# BLL-EBOOK-RpiZero.net
KiCad netlist of a schematic drawn in EAGLE
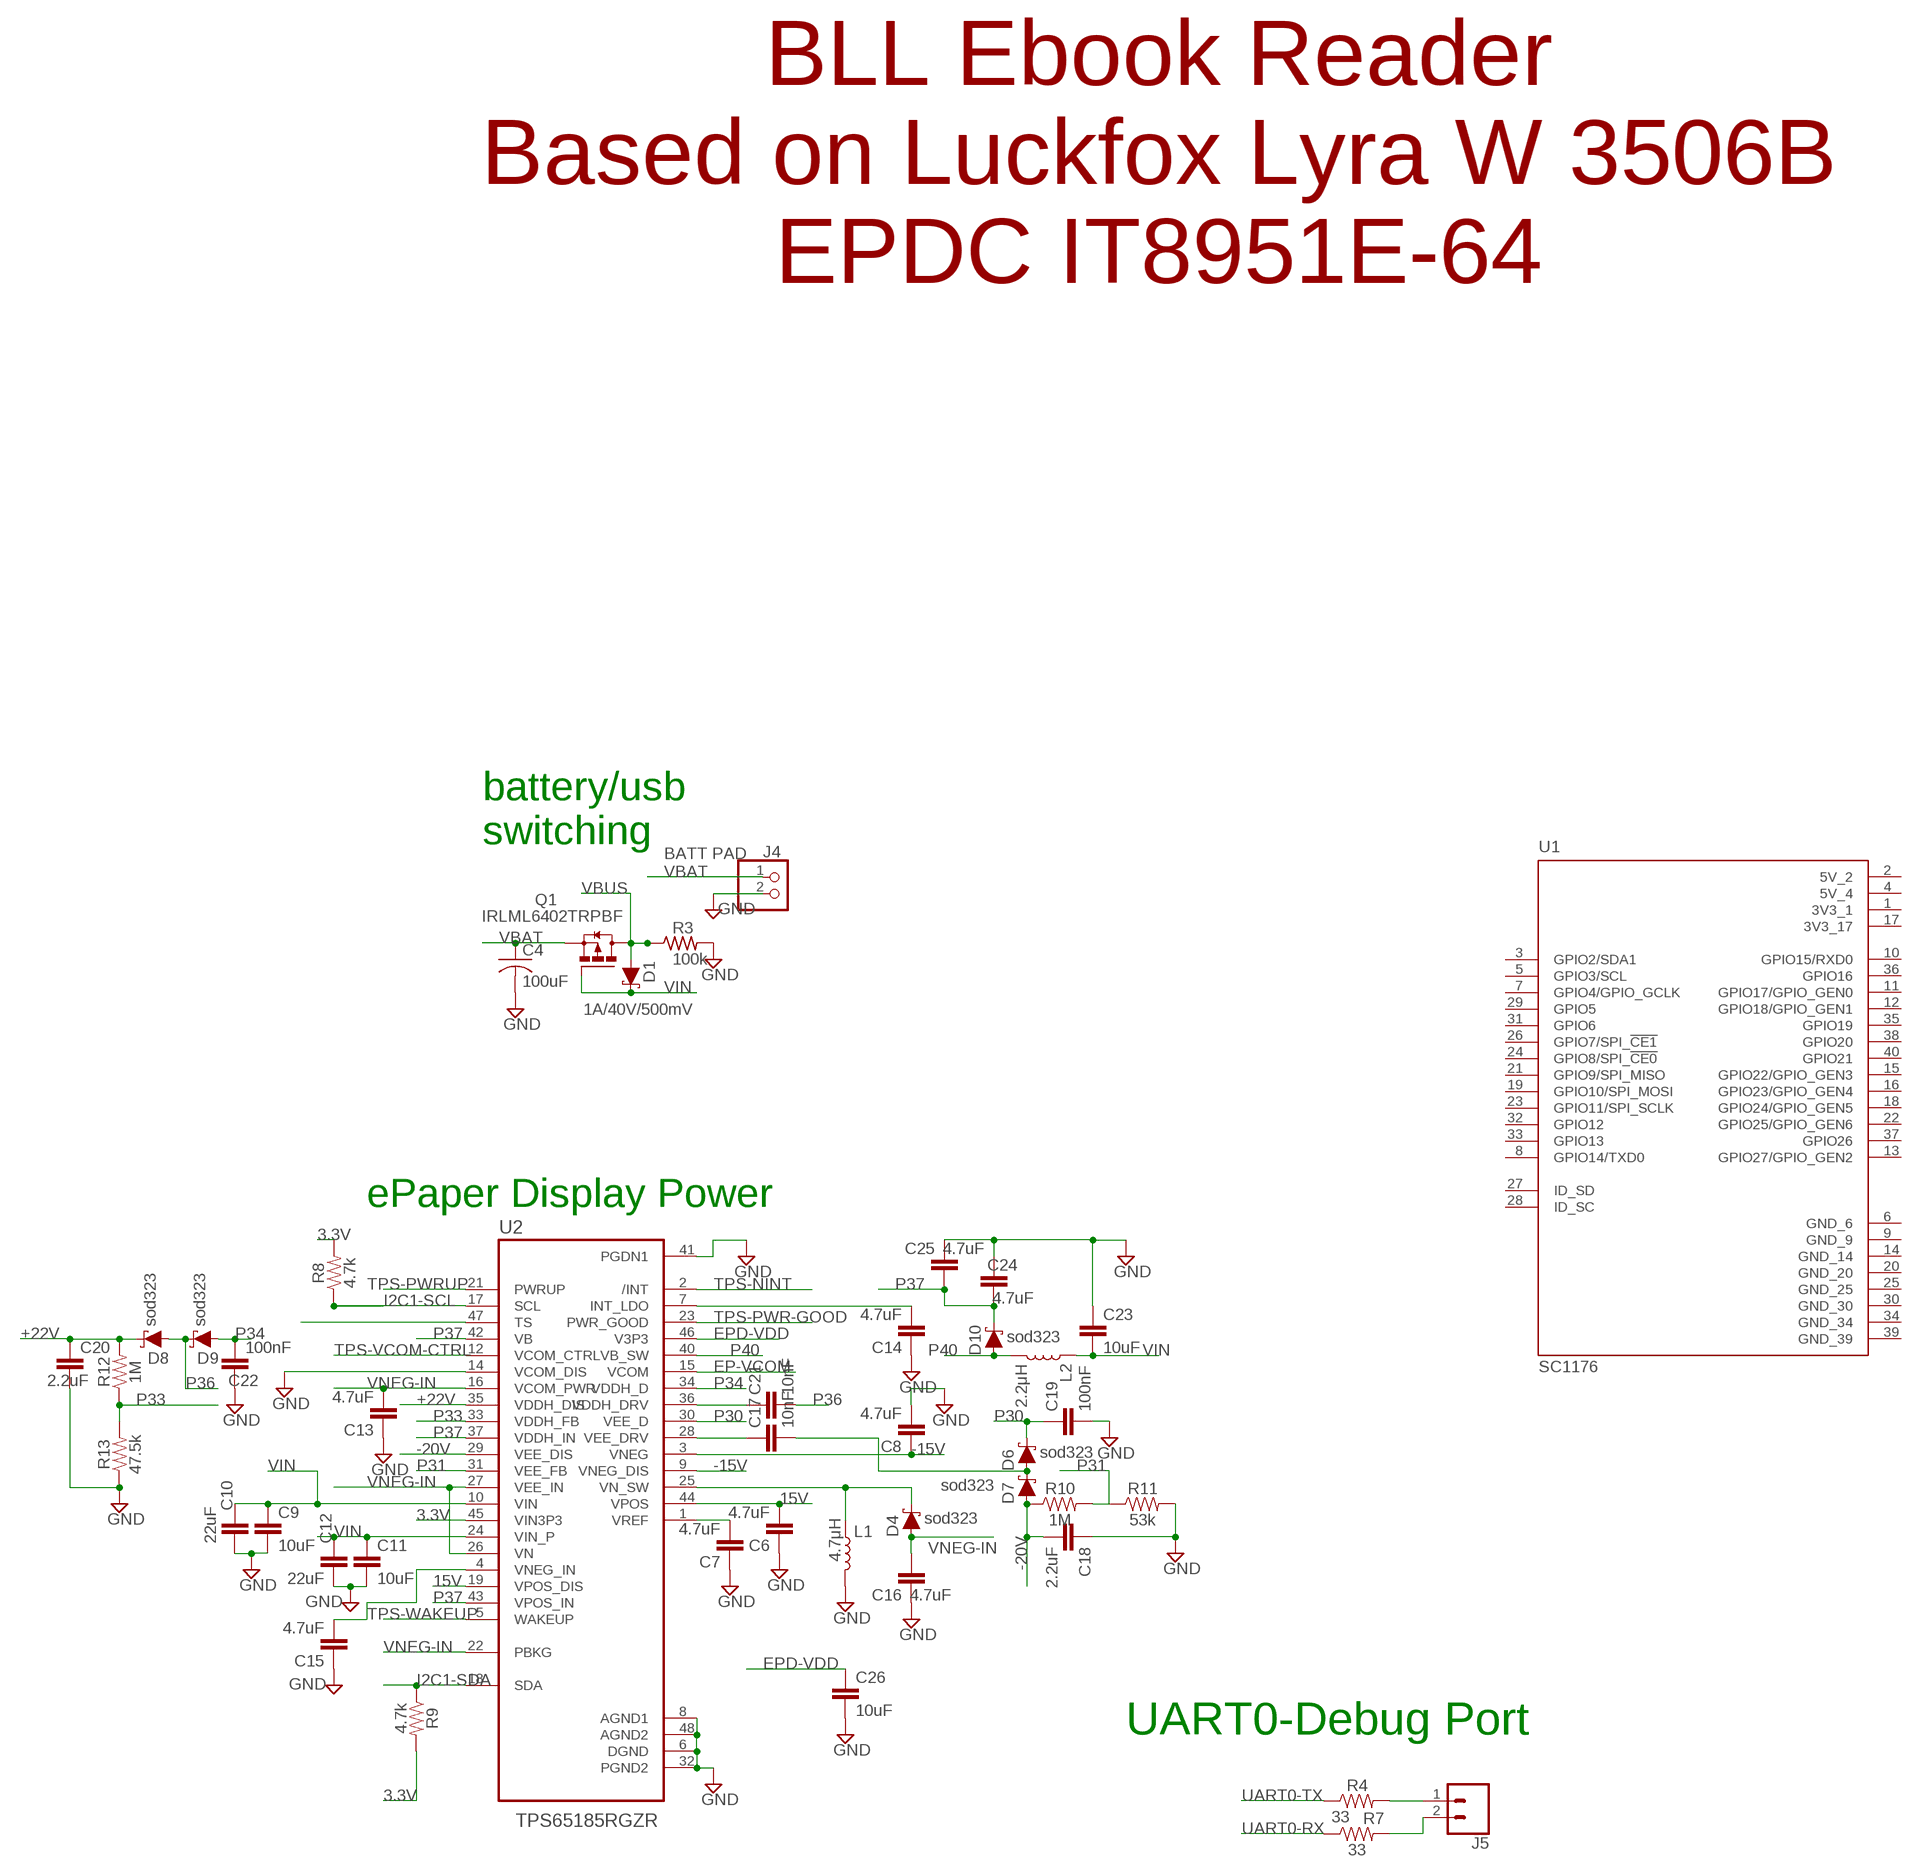
[diagram p0: schematic, sheet 1, part 1 of 2]
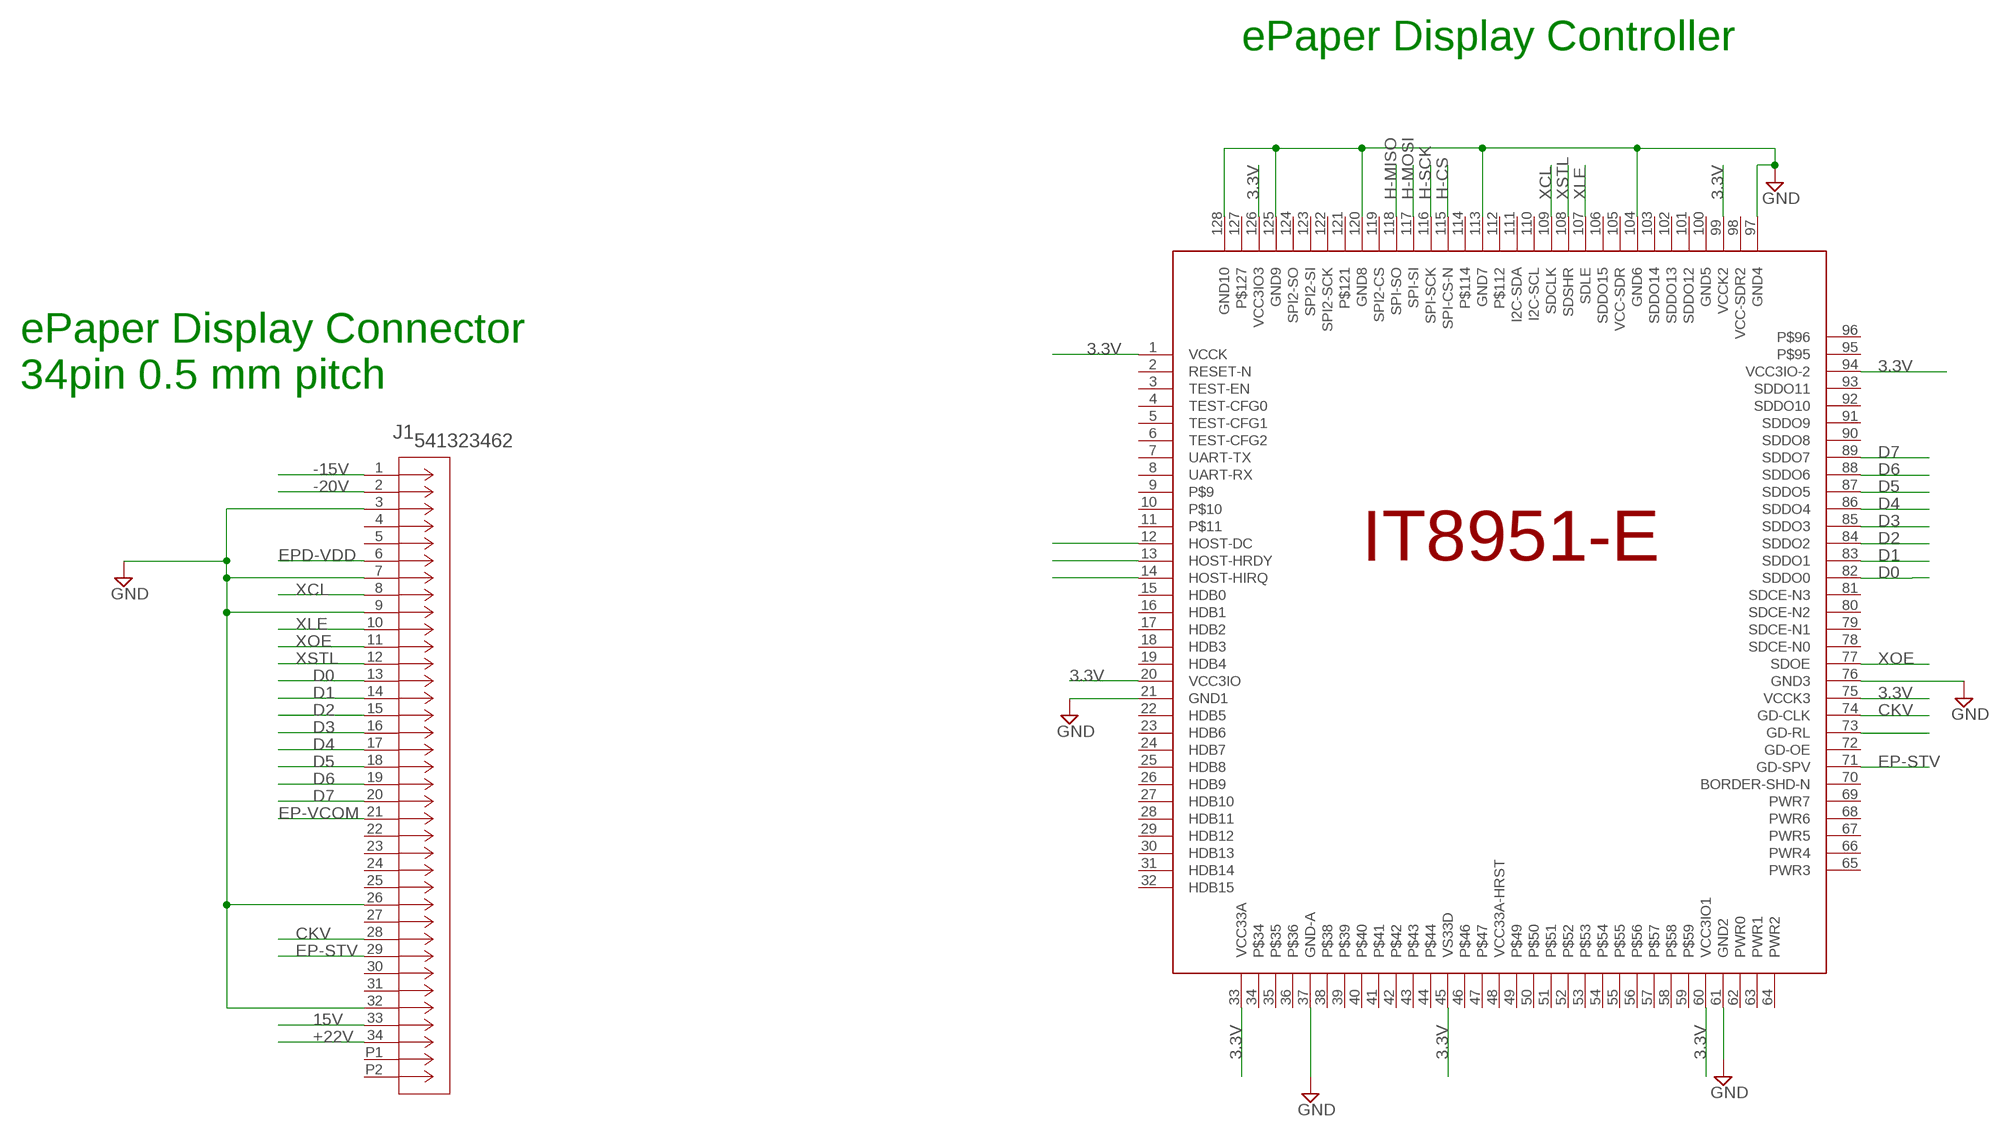
[diagram p1: schematic, sheet 1, part 2 of 2]

(export (version "E")
  (design (tool "Eeschema 10.0.6"))
  (components
    (comp (ref "C4")
      (value "100uF")
      (footprint "eagle-import:C0603")
      (libsource (lib "eagle-import") (part "C-USC0603"))
    )
    (comp (ref "C6")
      (value "4.7uF")
      (footprint "eagle-import:0603")
      (libsource (lib "eagle-import") (part "4.7UF-0603-35V-(20%)"))
    )
    (comp (ref "C7")
      (value "4.7uF")
      (footprint "eagle-import:0603")
      (libsource (lib "eagle-import") (part "4.7UF-0603-35V-(20%)"))
    )
    (comp (ref "C8")
      (value "4.7uF")
      (footprint "eagle-import:0603")
      (libsource (lib "eagle-import") (part "4.7UF-0603-35V-(20%)"))
    )
    (comp (ref "C9")
      (value "10uF")
      (footprint "eagle-import:0805")
      (libsource (lib "eagle-import") (part "10UF-0805-10V-10%"))
    )
    (comp (ref "C10")
      (value "22uF")
      (footprint "eagle-import:0805")
      (libsource (lib "eagle-import") (part "22UF-0805-16V-20%"))
    )
    (comp (ref "C11")
      (value "10uF")
      (footprint "eagle-import:0805")
      (libsource (lib "eagle-import") (part "10UF-0805-10V-10%"))
    )
    (comp (ref "C12")
      (value "22uF")
      (footprint "eagle-import:0805")
      (libsource (lib "eagle-import") (part "22UF-0805-16V-20%"))
    )
    (comp (ref "C13")
      (value "4.7uF")
      (footprint "eagle-import:0603")
      (libsource (lib "eagle-import") (part "4.7UF-0603-35V-(20%)"))
    )
    (comp (ref "C14")
      (value "4.7uF")
      (footprint "eagle-import:0603")
      (libsource (lib "eagle-import") (part "4.7UF-0603-35V-(20%)"))
    )
    (comp (ref "C15")
      (value "4.7uF")
      (footprint "eagle-import:0603")
      (libsource (lib "eagle-import") (part "4.7UF-0603-35V-(20%)"))
    )
    (comp (ref "C16")
      (value "4.7uF")
      (footprint "eagle-import:0603")
      (libsource (lib "eagle-import") (part "4.7UF-0603-35V-(20%)"))
    )
    (comp (ref "C17")
      (value "10nF")
      (footprint "eagle-import:0603")
      (libsource (lib "eagle-import") (part "10NF-0603-50V-10%"))
    )
    (comp (ref "C18")
      (value "2.2uF")
      (footprint "eagle-import:1206")
      (libsource (lib "eagle-import") (part "2.2UF-1206-50V-10%"))
    )
    (comp (ref "C19")
      (value "100nF")
      (footprint "eagle-import:0603")
      (libsource (lib "eagle-import") (part "DNP-0603"))
    )
    (comp (ref "C20")
      (value "2.2uF")
      (footprint "eagle-import:1206")
      (libsource (lib "eagle-import") (part "2.2UF-1206-50V-10%"))
    )
    (comp (ref "C21")
      (value "10nF")
      (footprint "eagle-import:0603")
      (libsource (lib "eagle-import") (part "10NF-0603-50V-10%"))
    )
    (comp (ref "C22")
      (value "100nF")
      (footprint "eagle-import:0603")
      (libsource (lib "eagle-import") (part "DNP-0603"))
    )
    (comp (ref "C23")
      (value "10uF")
      (footprint "eagle-import:0805")
      (libsource (lib "eagle-import") (part "10UF-0805-10V-10%"))
    )
    (comp (ref "C24")
      (value "4.7uF")
      (footprint "eagle-import:0603")
      (libsource (lib "eagle-import") (part "4.7UF-0603-35V-(20%)"))
    )
    (comp (ref "C25")
      (value "4.7uF")
      (footprint "eagle-import:0603")
      (libsource (lib "eagle-import") (part "4.7UF-0603-35V-(20%)"))
    )
    (comp (ref "C26")
      (value "10uF")
      (footprint "eagle-import:0805")
      (libsource (lib "eagle-import") (part "10UF-0805-10V-10%"))
    )
    (comp (ref "D1")
      (value "1A/40V/500mV")
      (footprint "eagle-import:SMA-DIODE")
      (libsource (lib "eagle-import") (part "DIODE-SCHOTTKY-SS14"))
    )
    (comp (ref "D4")
      (value "sod323")
      (footprint "eagle-import:SOD-323")
      (libsource (lib "eagle-import") (part "DIODE-SCHOTTKY-PMEG4005EJ"))
    )
    (comp (ref "D6")
      (value "sod323")
      (footprint "eagle-import:SOD-323")
      (libsource (lib "eagle-import") (part "DIODE-SCHOTTKY-PMEG4005EJ"))
    )
    (comp (ref "D7")
      (value "sod323")
      (footprint "eagle-import:SOD-323")
      (libsource (lib "eagle-import") (part "DIODE-SCHOTTKY-PMEG4005EJ"))
    )
    (comp (ref "D8")
      (value "sod323")
      (footprint "eagle-import:SOD-323")
      (libsource (lib "eagle-import") (part "DIODE-SCHOTTKY-PMEG4005EJ"))
    )
    (comp (ref "D9")
      (value "sod323")
      (footprint "eagle-import:SOD-323")
      (libsource (lib "eagle-import") (part "DIODE-SCHOTTKY-PMEG4005EJ"))
    )
    (comp (ref "D10")
      (value "sod323")
      (footprint "eagle-import:SOD-323")
      (libsource (lib "eagle-import") (part "DIODE-SCHOTTKY-PMEG4005EJ"))
    )
    (comp (ref "J1")
      (value "541323462")
      (footprint "eagle-import:CON_541323462_MOL")
      (fields (field (name "MF") "Molex"))
      (libsource (lib "eagle-import") (part "541323462"))
    )
    (comp (ref "J4")
      (value "BATT PAD")
      (footprint "eagle-import:1X02_90")
      (libsource (lib "eagle-import") (part "PINHD-1X2/90"))
    )
    (comp (ref "J5")
      (value "CONN_02LOCK")
      (footprint "eagle-import:1X02_LOCK")
      (libsource (lib "eagle-import") (part "CONN_02LOCK"))
    )
    (comp (ref "L1")
      (value "4.7μH")
      (footprint "eagle-import:1008(2520)")
      (libsource (lib "eagle-import") (part "4.7μH_SHIELDED_INDUCTOR"))
    )
    (comp (ref "L2")
      (value "2.2μH")
      (footprint "eagle-import:0806")
      (libsource (lib "eagle-import") (part "2.2μH_SHIELDED_INDUCTOR"))
    )
    (comp (ref "Q1")
      (value "IRLML6402TRPBF")
      (footprint "eagle-import:SOT23")
      (fields (field (name "MF") "Infineon Technologies") (field (name "MP") "IRLML6402"))
      (libsource (lib "eagle-import") (part "IRLML6402TRPBF"))
    )
    (comp (ref "R3")
      (value "100k")
      (footprint "eagle-import:R0603")
      (libsource (lib "eagle-import") (part "R-US_R0603"))
    )
    (comp (ref "R4")
      (value "33")
      (footprint "eagle-import:0603")
      (libsource (lib "eagle-import") (part "33OHM-0603-1/10W-1%"))
    )
    (comp (ref "R7")
      (value "33")
      (footprint "eagle-import:0603")
      (libsource (lib "eagle-import") (part "33OHM-0603-1/10W-1%"))
    )
    (comp (ref "R8")
      (value "4.7k")
      (footprint "eagle-import:0603")
      (libsource (lib "eagle-import") (part "4.7KOHM-0603-1/10W-1%"))
    )
    (comp (ref "R9")
      (value "4.7k")
      (footprint "eagle-import:0603")
      (libsource (lib "eagle-import") (part "4.7KOHM-0603-1/10W-1%"))
    )
    (comp (ref "R10")
      (value "1M")
      (footprint "eagle-import:0603")
      (libsource (lib "eagle-import") (part "1MOHM-0603-1/4W-5%"))
    )
    (comp (ref "R11")
      (value "53k")
      (footprint "eagle-import:0805")
      (libsource (lib "eagle-import") (part "RESISTOR0805"))
    )
    (comp (ref "R12")
      (value "1M")
      (footprint "eagle-import:0603")
      (libsource (lib "eagle-import") (part "1MOHM-0603-1/4W-5%"))
    )
    (comp (ref "R13")
      (value "47.5k")
      (footprint "eagle-import:0805")
      (libsource (lib "eagle-import") (part "RESISTOR0805"))
    )
    (comp (ref "U$1")
      (value "IT8951")
      (footprint "eagle-import:LQFP128_STM")
      (libsource (lib "eagle-import") (part "IT8951"))
    )
    (comp (ref "U1")
      (value "SC1176")
      (footprint "eagle-import:MODULE_SC1176")
      (fields (field (name "MF") "Raspberry Pi"))
      (libsource (lib "eagle-import") (part "SC1176"))
    )
    (comp (ref "U2")
      (value "TPS65185RGZR")
      (footprint "eagle-import:QFN50P700X700X100-49N")
      (fields (field (name "MF") "Texas Instruments"))
      (libsource (lib "eagle-import") (part "TPS65185RGZR"))
    )
  )
  (nets
    (net (code "1") (name "/+22V") (class "Default")
      (node (ref "C20") (pin "1") (pinfunction "1_1") (pintype "passive"))
      (node (ref "D8") (pin "C") (pinfunction "C_C") (pintype "passive"))
      (node (ref "J1") (pin "34") (pinfunction "34_34") (pintype "passive"))
      (node (ref "R12") (pin "2") (pinfunction "2_2") (pintype "passive"))
      (node (ref "U2") (pin "35") (pinfunction "VDDH_DIS_35") (pintype "input"))
    )
    (net (code "2") (name "/-15V") (class "Default")
      (node (ref "C8") (pin "1") (pinfunction "1_1") (pintype "passive"))
      (node (ref "J1") (pin "1") (pinfunction "1_1") (pintype "passive"))
      (node (ref "U2") (pin "3") (pinfunction "VNEG_3") (pintype "output"))
      (node (ref "U2") (pin "9") (pinfunction "VNEG_DIS_9") (pintype "output"))
    )
    (net (code "3") (name "/-20V") (class "Default")
      (node (ref "C18") (pin "2") (pinfunction "2_2") (pintype "passive"))
      (node (ref "D7") (pin "A") (pinfunction "A_A") (pintype "passive"))
      (node (ref "J1") (pin "2") (pinfunction "2_2") (pintype "passive"))
      (node (ref "R10") (pin "1") (pinfunction "1_1") (pintype "passive"))
      (node (ref "U2") (pin "29") (pinfunction "VEE_DIS_29") (pintype "input"))
    )
    (net (code "4") (name "/3.3V") (class "Default")
      (node (ref "R8") (pin "2") (pinfunction "2_2") (pintype "passive"))
      (node (ref "R9") (pin "2") (pinfunction "2_2") (pintype "passive"))
      (node (ref "U$1") (pin "1") (pinfunction "VCCK_1") (pintype "bidirectional"))
      (node (ref "U$1") (pin "126") (pinfunction "VCC3IO3_126") (pintype "bidirectional"))
      (node (ref "U$1") (pin "20") (pinfunction "VCC3IO_20") (pintype "bidirectional"))
      (node (ref "U$1") (pin "33") (pinfunction "VCC33A_33") (pintype "bidirectional"))
      (node (ref "U$1") (pin "45") (pinfunction "VS33D_45") (pintype "bidirectional"))
      (node (ref "U$1") (pin "60") (pinfunction "VCC3IO1_60") (pintype "bidirectional"))
      (node (ref "U$1") (pin "75") (pinfunction "VCCK3_75") (pintype "bidirectional"))
      (node (ref "U$1") (pin "94") (pinfunction "VCC3IO-2_94") (pintype "bidirectional"))
      (node (ref "U$1") (pin "99") (pinfunction "VCCK2_99") (pintype "bidirectional"))
      (node (ref "U2") (pin "45") (pinfunction "VIN3P3_45") (pintype "input"))
    )
    (net (code "5") (name "/3V3_1") (class "Default")
      (node (ref "U1") (pin "1") (pinfunction "3V3_1_1") (pintype "power_in"))
    )
    (net (code "6") (name "/3V3_17") (class "Default")
      (node (ref "U1") (pin "17") (pinfunction "3V3_17_17") (pintype "power_in"))
    )
    (net (code "7") (name "/5V_2") (class "Default")
      (node (ref "U1") (pin "2") (pinfunction "5V_2_2") (pintype "power_in"))
    )
    (net (code "8") (name "/5V_4") (class "Default")
      (node (ref "U1") (pin "4") (pinfunction "5V_4_4") (pintype "power_in"))
    )
    (net (code "9") (name "/15V") (class "Default")
      (node (ref "C6") (pin "2") (pinfunction "2_2") (pintype "passive"))
      (node (ref "J1") (pin "33") (pinfunction "33_33") (pintype "passive"))
      (node (ref "U2") (pin "19") (pinfunction "VPOS_DIS_19") (pintype "input"))
      (node (ref "U2") (pin "44") (pinfunction "VPOS_44") (pintype "output"))
    )
    (net (code "10") (name "/CKV") (class "Default")
      (node (ref "J1") (pin "28") (pinfunction "28_28") (pintype "passive"))
      (node (ref "U$1") (pin "74") (pinfunction "GD-CLK_74") (pintype "bidirectional"))
    )
    (net (code "11") (name "/D0") (class "Default")
      (node (ref "J1") (pin "13") (pinfunction "13_13") (pintype "passive"))
      (node (ref "U$1") (pin "82") (pinfunction "SDDO0_82") (pintype "bidirectional"))
    )
    (net (code "12") (name "/D1") (class "Default")
      (node (ref "J1") (pin "14") (pinfunction "14_14") (pintype "passive"))
      (node (ref "U$1") (pin "83") (pinfunction "SDDO1_83") (pintype "bidirectional"))
    )
    (net (code "13") (name "/D2") (class "Default")
      (node (ref "J1") (pin "15") (pinfunction "15_15") (pintype "passive"))
      (node (ref "U$1") (pin "84") (pinfunction "SDDO2_84") (pintype "bidirectional"))
    )
    (net (code "14") (name "/D3") (class "Default")
      (node (ref "J1") (pin "16") (pinfunction "16_16") (pintype "passive"))
      (node (ref "U$1") (pin "85") (pinfunction "SDDO3_85") (pintype "bidirectional"))
    )
    (net (code "15") (name "/D4") (class "Default")
      (node (ref "J1") (pin "17") (pinfunction "17_17") (pintype "passive"))
      (node (ref "U$1") (pin "86") (pinfunction "SDDO4_86") (pintype "bidirectional"))
    )
    (net (code "16") (name "/D5") (class "Default")
      (node (ref "J1") (pin "18") (pinfunction "18_18") (pintype "passive"))
      (node (ref "U$1") (pin "87") (pinfunction "SDDO5_87") (pintype "bidirectional"))
    )
    (net (code "17") (name "/D6") (class "Default")
      (node (ref "J1") (pin "19") (pinfunction "19_19") (pintype "passive"))
      (node (ref "U$1") (pin "88") (pinfunction "SDDO6_88") (pintype "bidirectional"))
    )
    (net (code "18") (name "/D7") (class "Default")
      (node (ref "J1") (pin "20") (pinfunction "20_20") (pintype "passive"))
      (node (ref "U$1") (pin "89") (pinfunction "SDDO7_89") (pintype "bidirectional"))
    )
    (net (code "19") (name "/EP-STV") (class "Default")
      (node (ref "J1") (pin "29") (pinfunction "29_29") (pintype "passive"))
      (node (ref "U$1") (pin "71") (pinfunction "GD-SPV_71") (pintype "bidirectional"))
    )
    (net (code "20") (name "/EP-VCOM") (class "Default")
      (node (ref "J1") (pin "21") (pinfunction "21_21") (pintype "passive"))
      (node (ref "U2") (pin "15") (pinfunction "VCOM_15") (pintype "output"))
    )
    (net (code "21") (name "/EPD-VDD") (class "Default")
      (node (ref "C26") (pin "1") (pinfunction "1_1") (pintype "passive"))
      (node (ref "J1") (pin "6") (pinfunction "6_6") (pintype "passive"))
      (node (ref "U2") (pin "46") (pinfunction "V3P3_46") (pintype "output"))
    )
    (net (code "22") (name "/GND_6") (class "Default")
      (node (ref "U1") (pin "6") (pinfunction "GND_6_6") (pintype "power_in"))
    )
    (net (code "23") (name "/GND_9") (class "Default")
      (node (ref "U1") (pin "9") (pinfunction "GND_9_9") (pintype "power_in"))
    )
    (net (code "24") (name "/GND_14") (class "Default")
      (node (ref "U1") (pin "14") (pinfunction "GND_14_14") (pintype "power_in"))
    )
    (net (code "25") (name "/GND_20") (class "Default")
      (node (ref "U1") (pin "20") (pinfunction "GND_20_20") (pintype "power_in"))
    )
    (net (code "26") (name "/GND_25") (class "Default")
      (node (ref "U1") (pin "25") (pinfunction "GND_25_25") (pintype "power_in"))
    )
    (net (code "27") (name "/GND_30") (class "Default")
      (node (ref "U1") (pin "30") (pinfunction "GND_30_30") (pintype "power_in"))
    )
    (net (code "28") (name "/GND_34") (class "Default")
      (node (ref "U1") (pin "34") (pinfunction "GND_34_34") (pintype "power_in"))
    )
    (net (code "29") (name "/GND_39") (class "Default")
      (node (ref "U1") (pin "39") (pinfunction "GND_39_39") (pintype "power_in"))
    )
    (net (code "30") (name "/H-CS") (class "Default")
      (node (ref "U$1") (pin "115") (pinfunction "SPI-CS-N_115") (pintype "bidirectional"))
    )
    (net (code "31") (name "/H-MISO") (class "Default")
      (node (ref "U$1") (pin "118") (pinfunction "SPI-SO_118") (pintype "bidirectional"))
    )
    (net (code "32") (name "/H-MOSI") (class "Default")
      (node (ref "U$1") (pin "117") (pinfunction "SPI-SI_117") (pintype "bidirectional"))
    )
    (net (code "33") (name "/H-SCK") (class "Default")
      (node (ref "U$1") (pin "116") (pinfunction "SPI-SCK_116") (pintype "bidirectional"))
    )
    (net (code "34") (name "/I2C1-SCL") (class "Default")
      (node (ref "R8") (pin "1") (pinfunction "1_1") (pintype "passive"))
      (node (ref "U2") (pin "17") (pinfunction "SCL_17") (pintype "input"))
    )
    (net (code "35") (name "/I2C1-SDA") (class "Default")
      (node (ref "R9") (pin "1") (pinfunction "1_1") (pintype "passive"))
      (node (ref "U2") (pin "18") (pinfunction "SDA_18") (pintype "bidirectional"))
    )
    (net (code "36") (name "/P30") (class "Default")
      (node (ref "C19") (pin "1") (pinfunction "1_1") (pintype "passive"))
      (node (ref "D6") (pin "C") (pinfunction "C_C") (pintype "passive"))
      (node (ref "U2") (pin "30") (pinfunction "VEE_D_30") (pintype "output"))
    )
    (net (code "37") (name "/P31") (class "Default")
      (node (ref "R10") (pin "2") (pinfunction "2_2") (pintype "passive"))
      (node (ref "R11") (pin "1") (pinfunction "1_1") (pintype "passive"))
      (node (ref "U2") (pin "31") (pinfunction "VEE_FB_31") (pintype "input"))
    )
    (net (code "38") (name "/P33") (class "Default")
      (node (ref "R12") (pin "1") (pinfunction "1_1") (pintype "passive"))
      (node (ref "R13") (pin "2") (pinfunction "2_2") (pintype "passive"))
      (node (ref "U2") (pin "33") (pinfunction "VDDH_FB_33") (pintype "input"))
    )
    (net (code "39") (name "/P34") (class "Default")
      (node (ref "C22") (pin "2") (pinfunction "2_2") (pintype "passive"))
      (node (ref "D9") (pin "A") (pinfunction "A_A") (pintype "passive"))
      (node (ref "U2") (pin "34") (pinfunction "VDDH_D_34") (pintype "output"))
    )
    (net (code "40") (name "/P36") (class "Default")
      (node (ref "C21") (pin "2") (pinfunction "2_2") (pintype "passive"))
      (node (ref "D8") (pin "A") (pinfunction "A_A") (pintype "passive"))
      (node (ref "D9") (pin "C") (pinfunction "C_C") (pintype "passive"))
    )
    (net (code "41") (name "/P37") (class "Default")
      (node (ref "C24") (pin "1") (pinfunction "1_1") (pintype "passive"))
      (node (ref "C25") (pin "1") (pinfunction "1_1") (pintype "passive"))
      (node (ref "D10") (pin "C") (pinfunction "C_C") (pintype "passive"))
      (node (ref "U2") (pin "37") (pinfunction "VDDH_IN_37") (pintype "input"))
      (node (ref "U2") (pin "42") (pinfunction "VB_42") (pintype "input"))
      (node (ref "U2") (pin "43") (pinfunction "VPOS_IN_43") (pintype "input"))
    )
    (net (code "42") (name "/P40") (class "Default")
      (node (ref "D10") (pin "A") (pinfunction "A_A") (pintype "passive"))
      (node (ref "L2") (pin "2") (pinfunction "2_2") (pintype "passive"))
      (node (ref "U2") (pin "40") (pinfunction "VB_SW_40") (pintype "output"))
    )
    (net (code "43") (name "/TPS-NINT") (class "Default")
      (node (ref "U2") (pin "2") (pinfunction "/INT_2") (pintype "output"))
    )
    (net (code "44") (name "/TPS-PWR-GOOD") (class "Default")
      (node (ref "U2") (pin "23") (pinfunction "PWR_GOOD_23") (pintype "output"))
    )
    (net (code "45") (name "/TPS-PWRUP") (class "Default")
      (node (ref "U2") (pin "21") (pinfunction "PWRUP_21") (pintype "input"))
    )
    (net (code "46") (name "/TPS-VCOM-CTRL") (class "Default")
      (node (ref "U2") (pin "12") (pinfunction "VCOM_CTRL_12") (pintype "input"))
    )
    (net (code "47") (name "/TPS-WAKEUP") (class "Default")
      (node (ref "U2") (pin "5") (pinfunction "WAKEUP_5") (pintype "input"))
    )
    (net (code "48") (name "/UART0-RX") (class "Default")
      (node (ref "R7") (pin "1") (pinfunction "1_1") (pintype "passive"))
    )
    (net (code "49") (name "/UART0-TX") (class "Default")
      (node (ref "R4") (pin "1") (pinfunction "1_1") (pintype "passive"))
    )
    (net (code "50") (name "/VBAT") (class "Default")
      (node (ref "C4") (pin "1") (pinfunction "1_1") (pintype "passive"))
      (node (ref "J4") (pin "1") (pinfunction "1_1") (pintype "passive"))
      (node (ref "Q1") (pin "2") (pinfunction "S_2") (pintype "passive"))
    )
    (net (code "51") (name "/VBUS") (class "Default")
      (node (ref "D1") (pin "A") (pinfunction "A_A") (pintype "passive"))
      (node (ref "Q1") (pin "3") (pinfunction "D_3") (pintype "passive"))
      (node (ref "R3") (pin "1") (pinfunction "1_1") (pintype "passive"))
    )
    (net (code "52") (name "/VIN") (class "Default")
      (node (ref "C10") (pin "1") (pinfunction "1_1") (pintype "passive"))
      (node (ref "C11") (pin "1") (pinfunction "1_1") (pintype "passive"))
      (node (ref "C12") (pin "1") (pinfunction "1_1") (pintype "passive"))
      (node (ref "C23") (pin "2") (pinfunction "2_2") (pintype "passive"))
      (node (ref "C9") (pin "1") (pinfunction "1_1") (pintype "passive"))
      (node (ref "D1") (pin "C") (pinfunction "C_C") (pintype "passive"))
      (node (ref "L2") (pin "1") (pinfunction "1_1") (pintype "passive"))
      (node (ref "Q1") (pin "1") (pinfunction "G_1") (pintype "passive"))
      (node (ref "U2") (pin "10") (pinfunction "VIN_10") (pintype "input"))
      (node (ref "U2") (pin "24") (pinfunction "VIN_P_24") (pintype "input"))
    )
    (net (code "53") (name "/VNEG-IN") (class "Default")
      (node (ref "C13") (pin "2") (pinfunction "2_2") (pintype "passive"))
      (node (ref "C16") (pin "2") (pinfunction "2_2") (pintype "passive"))
      (node (ref "D4") (pin "A") (pinfunction "A_A") (pintype "passive"))
      (node (ref "U2") (pin "16") (pinfunction "VCOM_PWR_16") (pintype "input"))
      (node (ref "U2") (pin "22") (pinfunction "PBKG_22") (pintype "bidirectional"))
      (node (ref "U2") (pin "26") (pinfunction "VN_26") (pintype "input"))
      (node (ref "U2") (pin "27") (pinfunction "VEE_IN_27") (pintype "input"))
    )
    (net (code "54") (name "/XCL") (class "Default")
      (node (ref "J1") (pin "8") (pinfunction "8_8") (pintype "passive"))
      (node (ref "U$1") (pin "109") (pinfunction "SDCLK_109") (pintype "bidirectional"))
    )
    (net (code "55") (name "/XLE") (class "Default")
      (node (ref "J1") (pin "10") (pinfunction "10_10") (pintype "passive"))
      (node (ref "U$1") (pin "107") (pinfunction "SDLE_107") (pintype "bidirectional"))
    )
    (net (code "56") (name "/XOE") (class "Default")
      (node (ref "J1") (pin "11") (pinfunction "11_11") (pintype "passive"))
      (node (ref "U$1") (pin "77") (pinfunction "SDOE_77") (pintype "bidirectional"))
    )
    (net (code "57") (name "/XSTL") (class "Default")
      (node (ref "J1") (pin "12") (pinfunction "12_12") (pintype "passive"))
      (node (ref "U$1") (pin "108") (pinfunction "SDSHR_108") (pintype "bidirectional"))
    )
    (net (code "58") (name "GND") (class "Default")
      (node (ref "C10") (pin "2") (pinfunction "2_2") (pintype "passive"))
      (node (ref "C11") (pin "2") (pinfunction "2_2") (pintype "passive"))
      (node (ref "C12") (pin "2") (pinfunction "2_2") (pintype "passive"))
      (node (ref "C13") (pin "1") (pinfunction "1_1") (pintype "passive"))
      (node (ref "C14") (pin "1") (pinfunction "1_1") (pintype "passive"))
      (node (ref "C15") (pin "1") (pinfunction "1_1") (pintype "passive"))
      (node (ref "C16") (pin "1") (pinfunction "1_1") (pintype "passive"))
      (node (ref "C18") (pin "1") (pinfunction "1_1") (pintype "passive"))
      (node (ref "C19") (pin "2") (pinfunction "2_2") (pintype "passive"))
      (node (ref "C20") (pin "2") (pinfunction "2_2") (pintype "passive"))
      (node (ref "C22") (pin "1") (pinfunction "1_1") (pintype "passive"))
      (node (ref "C23") (pin "1") (pinfunction "1_1") (pintype "passive"))
      (node (ref "C24") (pin "2") (pinfunction "2_2") (pintype "passive"))
      (node (ref "C25") (pin "2") (pinfunction "2_2") (pintype "passive"))
      (node (ref "C26") (pin "2") (pinfunction "2_2") (pintype "passive"))
      (node (ref "C4") (pin "2") (pinfunction "2_2") (pintype "passive"))
      (node (ref "C6") (pin "1") (pinfunction "1_1") (pintype "passive"))
      (node (ref "C7") (pin "1") (pinfunction "1_1") (pintype "passive"))
      (node (ref "C8") (pin "2") (pinfunction "2_2") (pintype "passive"))
      (node (ref "C9") (pin "2") (pinfunction "2_2") (pintype "passive"))
      (node (ref "J1") (pin "26") (pinfunction "26_26") (pintype "passive"))
      (node (ref "J1") (pin "3") (pinfunction "3_3") (pintype "passive"))
      (node (ref "J1") (pin "32") (pinfunction "32_32") (pintype "passive"))
      (node (ref "J1") (pin "7") (pinfunction "7_7") (pintype "passive"))
      (node (ref "J1") (pin "9") (pinfunction "9_9") (pintype "passive"))
      (node (ref "J4") (pin "2") (pinfunction "2_2") (pintype "passive"))
      (node (ref "L1") (pin "2") (pinfunction "2_2") (pintype "passive"))
      (node (ref "R11") (pin "2") (pinfunction "2_2") (pintype "passive"))
      (node (ref "R13") (pin "1") (pinfunction "1_1") (pintype "passive"))
      (node (ref "R3") (pin "2") (pinfunction "2_2") (pintype "passive"))
      (node (ref "U$1") (pin "104") (pinfunction "GND6_104") (pintype "bidirectional"))
      (node (ref "U$1") (pin "113") (pinfunction "GND7_113") (pintype "bidirectional"))
      (node (ref "U$1") (pin "120") (pinfunction "GND8_120") (pintype "bidirectional"))
      (node (ref "U$1") (pin "125") (pinfunction "GND9_125") (pintype "bidirectional"))
      (node (ref "U$1") (pin "128") (pinfunction "GND10_128") (pintype "bidirectional"))
      (node (ref "U$1") (pin "21") (pinfunction "GND1_21") (pintype "bidirectional"))
      (node (ref "U$1") (pin "37") (pinfunction "GND-A_37") (pintype "bidirectional"))
      (node (ref "U$1") (pin "61") (pinfunction "GND2_61") (pintype "bidirectional"))
      (node (ref "U$1") (pin "76") (pinfunction "GND3_76") (pintype "bidirectional"))
      (node (ref "U$1") (pin "97") (pinfunction "GND4_97") (pintype "bidirectional"))
      (node (ref "U2") (pin "14") (pinfunction "VCOM_DIS_14") (pintype "input"))
      (node (ref "U2") (pin "32") (pinfunction "PGND2_32") (pintype "power_in"))
      (node (ref "U2") (pin "41") (pinfunction "PGDN1_41") (pintype "power_in"))
      (node (ref "U2") (pin "48") (pinfunction "AGND2_48") (pintype "power_in"))
      (node (ref "U2") (pin "6") (pinfunction "DGND_6") (pintype "power_in"))
      (node (ref "U2") (pin "8") (pinfunction "AGND1_8") (pintype "power_in"))
    )
    (net (code "59") (name "Net-(C17-Pad2)") (class "Default")
      (node (ref "C17") (pin "2") (pinfunction "2_2") (pintype "passive"))
      (node (ref "D6") (pin "A") (pinfunction "A_A") (pintype "passive"))
      (node (ref "D7") (pin "C") (pinfunction "C_C") (pintype "passive"))
    )
    (net (code "60") (name "Net-(J5-Pad1)") (class "Default")
      (node (ref "J5") (pin "1") (pinfunction "1_1") (pintype "passive"))
      (node (ref "R4") (pin "2") (pinfunction "2_2") (pintype "passive"))
    )
    (net (code "61") (name "Net-(J5-Pad2)") (class "Default")
      (node (ref "J5") (pin "2") (pinfunction "2_2") (pintype "passive"))
      (node (ref "R7") (pin "2") (pinfunction "2_2") (pintype "passive"))
    )
    (net (code "62") (name "Net-(U2-INT_LDO)") (class "Default")
      (node (ref "C14") (pin "2") (pinfunction "2_2") (pintype "passive"))
      (node (ref "U2") (pin "7") (pinfunction "INT_LDO_7") (pintype "output"))
    )
    (net (code "63") (name "Net-(U2-VDDH_DRV)") (class "Default")
      (node (ref "C21") (pin "1") (pinfunction "1_1") (pintype "passive"))
      (node (ref "U2") (pin "36") (pinfunction "VDDH_DRV_36") (pintype "output"))
    )
    (net (code "64") (name "Net-(U2-VEE_DRV)") (class "Default")
      (node (ref "C17") (pin "1") (pinfunction "1_1") (pintype "passive"))
      (node (ref "U2") (pin "28") (pinfunction "VEE_DRV_28") (pintype "output"))
    )
    (net (code "65") (name "Net-(U2-VNEG_IN)") (class "Default")
      (node (ref "C15") (pin "2") (pinfunction "2_2") (pintype "passive"))
      (node (ref "U2") (pin "4") (pinfunction "VNEG_IN_4") (pintype "input"))
    )
    (net (code "66") (name "Net-(U2-VN_SW)") (class "Default")
      (node (ref "D4") (pin "C") (pinfunction "C_C") (pintype "passive"))
      (node (ref "L1") (pin "1") (pinfunction "1_1") (pintype "passive"))
      (node (ref "U2") (pin "25") (pinfunction "VN_SW_25") (pintype "output"))
    )
    (net (code "67") (name "Net-(U2-VREF)") (class "Default")
      (node (ref "C7") (pin "2") (pinfunction "2_2") (pintype "passive"))
      (node (ref "U2") (pin "1") (pinfunction "VREF_1") (pintype "output"))
    )
    (net (code "68") (name "unconnected-(J1-Pad4)") (class "Default")
      (node (ref "J1") (pin "4") (pinfunction "4_4") (pintype "passive"))
    )
    (net (code "69") (name "unconnected-(J1-Pad5)") (class "Default")
      (node (ref "J1") (pin "5") (pinfunction "5_5") (pintype "passive"))
    )
    (net (code "70") (name "unconnected-(J1-Pad22)") (class "Default")
      (node (ref "J1") (pin "22") (pinfunction "22_22") (pintype "passive"))
    )
    (net (code "71") (name "unconnected-(J1-Pad23)") (class "Default")
      (node (ref "J1") (pin "23") (pinfunction "23_23") (pintype "passive"))
    )
    (net (code "72") (name "unconnected-(J1-Pad24)") (class "Default")
      (node (ref "J1") (pin "24") (pinfunction "24_24") (pintype "passive"))
    )
    (net (code "73") (name "unconnected-(J1-Pad25)") (class "Default")
      (node (ref "J1") (pin "25") (pinfunction "25_25") (pintype "passive"))
    )
    (net (code "74") (name "unconnected-(J1-Pad27)") (class "Default")
      (node (ref "J1") (pin "27") (pinfunction "27_27") (pintype "passive"))
    )
    (net (code "75") (name "unconnected-(J1-Pad30)") (class "Default")
      (node (ref "J1") (pin "30") (pinfunction "30_30") (pintype "passive"))
    )
    (net (code "76") (name "unconnected-(J1-Pad31)") (class "Default")
      (node (ref "J1") (pin "31") (pinfunction "31_31") (pintype "passive"))
    )
    (net (code "77") (name "unconnected-(J1-PadP1)") (class "Default")
      (node (ref "J1") (pin "P1") (pinfunction "P1_P1") (pintype "passive"))
    )
    (net (code "78") (name "unconnected-(J1-PadP2)") (class "Default")
      (node (ref "J1") (pin "P2") (pinfunction "P2_P2") (pintype "passive"))
    )
    (net (code "79") (name "unconnected-(U$1-BORDER-SHD-N-Pad70)") (class "Default")
      (node (ref "U$1") (pin "70") (pinfunction "BORDER-SHD-N_70") (pintype "bidirectional"))
    )
    (net (code "80") (name "unconnected-(U$1-GD-OE-Pad72)") (class "Default")
      (node (ref "U$1") (pin "72") (pinfunction "GD-OE_72") (pintype "bidirectional"))
    )
    (net (code "81") (name "unconnected-(U$1-GD-RL-Pad73)") (class "Default")
      (node (ref "U$1") (pin "73") (pinfunction "GD-RL_73") (pintype "bidirectional"))
    )
    (net (code "82") (name "unconnected-(U$1-GND5-Pad100)") (class "Default")
      (node (ref "U$1") (pin "100") (pinfunction "GND5_100") (pintype "bidirectional"))
    )
    (net (code "83") (name "unconnected-(U$1-HDB0-Pad15)") (class "Default")
      (node (ref "U$1") (pin "15") (pinfunction "HDB0_15") (pintype "bidirectional"))
    )
    (net (code "84") (name "unconnected-(U$1-HDB1-Pad16)") (class "Default")
      (node (ref "U$1") (pin "16") (pinfunction "HDB1_16") (pintype "bidirectional"))
    )
    (net (code "85") (name "unconnected-(U$1-HDB2-Pad17)") (class "Default")
      (node (ref "U$1") (pin "17") (pinfunction "HDB2_17") (pintype "bidirectional"))
    )
    (net (code "86") (name "unconnected-(U$1-HDB3-Pad18)") (class "Default")
      (node (ref "U$1") (pin "18") (pinfunction "HDB3_18") (pintype "bidirectional"))
    )
    (net (code "87") (name "unconnected-(U$1-HDB4-Pad19)") (class "Default")
      (node (ref "U$1") (pin "19") (pinfunction "HDB4_19") (pintype "bidirectional"))
    )
    (net (code "88") (name "unconnected-(U$1-HDB5-Pad22)") (class "Default")
      (node (ref "U$1") (pin "22") (pinfunction "HDB5_22") (pintype "bidirectional"))
    )
    (net (code "89") (name "unconnected-(U$1-HDB6-Pad23)") (class "Default")
      (node (ref "U$1") (pin "23") (pinfunction "HDB6_23") (pintype "bidirectional"))
    )
    (net (code "90") (name "unconnected-(U$1-HDB7-Pad24)") (class "Default")
      (node (ref "U$1") (pin "24") (pinfunction "HDB7_24") (pintype "bidirectional"))
    )
    (net (code "91") (name "unconnected-(U$1-HDB8-Pad25)") (class "Default")
      (node (ref "U$1") (pin "25") (pinfunction "HDB8_25") (pintype "bidirectional"))
    )
    (net (code "92") (name "unconnected-(U$1-HDB9-Pad26)") (class "Default")
      (node (ref "U$1") (pin "26") (pinfunction "HDB9_26") (pintype "bidirectional"))
    )
    (net (code "93") (name "unconnected-(U$1-HDB10-Pad27)") (class "Default")
      (node (ref "U$1") (pin "27") (pinfunction "HDB10_27") (pintype "bidirectional"))
    )
    (net (code "94") (name "unconnected-(U$1-HDB11-Pad28)") (class "Default")
      (node (ref "U$1") (pin "28") (pinfunction "HDB11_28") (pintype "bidirectional"))
    )
    (net (code "95") (name "unconnected-(U$1-HDB12-Pad29)") (class "Default")
      (node (ref "U$1") (pin "29") (pinfunction "HDB12_29") (pintype "bidirectional"))
    )
    (net (code "96") (name "unconnected-(U$1-HDB13-Pad30)") (class "Default")
      (node (ref "U$1") (pin "30") (pinfunction "HDB13_30") (pintype "bidirectional"))
    )
    (net (code "97") (name "unconnected-(U$1-HDB14-Pad31)") (class "Default")
      (node (ref "U$1") (pin "31") (pinfunction "HDB14_31") (pintype "bidirectional"))
    )
    (net (code "98") (name "unconnected-(U$1-HDB15-Pad32)") (class "Default")
      (node (ref "U$1") (pin "32") (pinfunction "HDB15_32") (pintype "bidirectional"))
    )
    (net (code "99") (name "unconnected-(U$1-HOST-DC-Pad12)") (class "Default")
      (node (ref "U$1") (pin "12") (pinfunction "HOST-DC_12") (pintype "bidirectional"))
    )
    (net (code "100") (name "unconnected-(U$1-HOST-HIRQ-Pad14)") (class "Default")
      (node (ref "U$1") (pin "14") (pinfunction "HOST-HIRQ_14") (pintype "bidirectional"))
    )
    (net (code "101") (name "unconnected-(U$1-HOST-HRDY-Pad13)") (class "Default")
      (node (ref "U$1") (pin "13") (pinfunction "HOST-HRDY_13") (pintype "bidirectional"))
    )
    (net (code "102") (name "unconnected-(U$1-I2C-SCL-Pad110)") (class "Default")
      (node (ref "U$1") (pin "110") (pinfunction "I2C-SCL_110") (pintype "bidirectional"))
    )
    (net (code "103") (name "unconnected-(U$1-I2C-SDA-Pad111)") (class "Default")
      (node (ref "U$1") (pin "111") (pinfunction "I2C-SDA_111") (pintype "bidirectional"))
    )
    (net (code "104") (name "unconnected-(U$1-P$9-Pad9)") (class "Default")
      (node (ref "U$1") (pin "9") (pinfunction "P$9_9") (pintype "bidirectional"))
    )
    (net (code "105") (name "unconnected-(U$1-P$10-Pad10)") (class "Default")
      (node (ref "U$1") (pin "10") (pinfunction "P$10_10") (pintype "bidirectional"))
    )
    (net (code "106") (name "unconnected-(U$1-P$11-Pad11)") (class "Default")
      (node (ref "U$1") (pin "11") (pinfunction "P$11_11") (pintype "bidirectional"))
    )
    (net (code "107") (name "unconnected-(U$1-P$34-Pad34)") (class "Default")
      (node (ref "U$1") (pin "34") (pinfunction "P$34_34") (pintype "bidirectional"))
    )
    (net (code "108") (name "unconnected-(U$1-P$35-Pad35)") (class "Default")
      (node (ref "U$1") (pin "35") (pinfunction "P$35_35") (pintype "bidirectional"))
    )
    (net (code "109") (name "unconnected-(U$1-P$36-Pad36)") (class "Default")
      (node (ref "U$1") (pin "36") (pinfunction "P$36_36") (pintype "bidirectional"))
    )
    (net (code "110") (name "unconnected-(U$1-P$38-Pad38)") (class "Default")
      (node (ref "U$1") (pin "38") (pinfunction "P$38_38") (pintype "bidirectional"))
    )
    (net (code "111") (name "unconnected-(U$1-P$39-Pad39)") (class "Default")
      (node (ref "U$1") (pin "39") (pinfunction "P$39_39") (pintype "bidirectional"))
    )
    (net (code "112") (name "unconnected-(U$1-P$40-Pad40)") (class "Default")
      (node (ref "U$1") (pin "40") (pinfunction "P$40_40") (pintype "bidirectional"))
    )
    (net (code "113") (name "unconnected-(U$1-P$41-Pad41)") (class "Default")
      (node (ref "U$1") (pin "41") (pinfunction "P$41_41") (pintype "bidirectional"))
    )
    (net (code "114") (name "unconnected-(U$1-P$42-Pad42)") (class "Default")
      (node (ref "U$1") (pin "42") (pinfunction "P$42_42") (pintype "bidirectional"))
    )
    (net (code "115") (name "unconnected-(U$1-P$43-Pad43)") (class "Default")
      (node (ref "U$1") (pin "43") (pinfunction "P$43_43") (pintype "bidirectional"))
    )
    (net (code "116") (name "unconnected-(U$1-P$44-Pad44)") (class "Default")
      (node (ref "U$1") (pin "44") (pinfunction "P$44_44") (pintype "bidirectional"))
    )
    (net (code "117") (name "unconnected-(U$1-P$46-Pad46)") (class "Default")
      (node (ref "U$1") (pin "46") (pinfunction "P$46_46") (pintype "bidirectional"))
    )
    (net (code "118") (name "unconnected-(U$1-P$47-Pad47)") (class "Default")
      (node (ref "U$1") (pin "47") (pinfunction "P$47_47") (pintype "bidirectional"))
    )
    (net (code "119") (name "unconnected-(U$1-P$49-Pad49)") (class "Default")
      (node (ref "U$1") (pin "49") (pinfunction "P$49_49") (pintype "bidirectional"))
    )
    (net (code "120") (name "unconnected-(U$1-P$50-Pad50)") (class "Default")
      (node (ref "U$1") (pin "50") (pinfunction "P$50_50") (pintype "bidirectional"))
    )
    (net (code "121") (name "unconnected-(U$1-P$51-Pad51)") (class "Default")
      (node (ref "U$1") (pin "51") (pinfunction "P$51_51") (pintype "bidirectional"))
    )
    (net (code "122") (name "unconnected-(U$1-P$52-Pad52)") (class "Default")
      (node (ref "U$1") (pin "52") (pinfunction "P$52_52") (pintype "bidirectional"))
    )
    (net (code "123") (name "unconnected-(U$1-P$53-Pad53)") (class "Default")
      (node (ref "U$1") (pin "53") (pinfunction "P$53_53") (pintype "bidirectional"))
    )
    (net (code "124") (name "unconnected-(U$1-P$54-Pad54)") (class "Default")
      (node (ref "U$1") (pin "54") (pinfunction "P$54_54") (pintype "bidirectional"))
    )
    (net (code "125") (name "unconnected-(U$1-P$55-Pad55)") (class "Default")
      (node (ref "U$1") (pin "55") (pinfunction "P$55_55") (pintype "bidirectional"))
    )
    (net (code "126") (name "unconnected-(U$1-P$56-Pad56)") (class "Default")
      (node (ref "U$1") (pin "56") (pinfunction "P$56_56") (pintype "bidirectional"))
    )
    (net (code "127") (name "unconnected-(U$1-P$57-Pad57)") (class "Default")
      (node (ref "U$1") (pin "57") (pinfunction "P$57_57") (pintype "bidirectional"))
    )
    (net (code "128") (name "unconnected-(U$1-P$58-Pad58)") (class "Default")
      (node (ref "U$1") (pin "58") (pinfunction "P$58_58") (pintype "bidirectional"))
    )
    (net (code "129") (name "unconnected-(U$1-P$59-Pad59)") (class "Default")
      (node (ref "U$1") (pin "59") (pinfunction "P$59_59") (pintype "bidirectional"))
    )
    (net (code "130") (name "unconnected-(U$1-P$95-Pad95)") (class "Default")
      (node (ref "U$1") (pin "95") (pinfunction "P$95_95") (pintype "bidirectional"))
    )
    (net (code "131") (name "unconnected-(U$1-P$96-Pad96)") (class "Default")
      (node (ref "U$1") (pin "96") (pinfunction "P$96_96") (pintype "bidirectional"))
    )
    (net (code "132") (name "unconnected-(U$1-P$112-Pad112)") (class "Default")
      (node (ref "U$1") (pin "112") (pinfunction "P$112_112") (pintype "bidirectional"))
    )
    (net (code "133") (name "unconnected-(U$1-P$114-Pad114)") (class "Default")
      (node (ref "U$1") (pin "114") (pinfunction "P$114_114") (pintype "bidirectional"))
    )
    (net (code "134") (name "unconnected-(U$1-P$121-Pad121)") (class "Default")
      (node (ref "U$1") (pin "121") (pinfunction "P$121_121") (pintype "bidirectional"))
    )
    (net (code "135") (name "unconnected-(U$1-P$127-Pad127)") (class "Default")
      (node (ref "U$1") (pin "127") (pinfunction "P$127_127") (pintype "bidirectional"))
    )
    (net (code "136") (name "unconnected-(U$1-PWR0-Pad62)") (class "Default")
      (node (ref "U$1") (pin "62") (pinfunction "PWR0_62") (pintype "bidirectional"))
    )
    (net (code "137") (name "unconnected-(U$1-PWR1-Pad63)") (class "Default")
      (node (ref "U$1") (pin "63") (pinfunction "PWR1_63") (pintype "bidirectional"))
    )
    (net (code "138") (name "unconnected-(U$1-PWR2-Pad64)") (class "Default")
      (node (ref "U$1") (pin "64") (pinfunction "PWR2_64") (pintype "bidirectional"))
    )
    (net (code "139") (name "unconnected-(U$1-PWR3-Pad65)") (class "Default")
      (node (ref "U$1") (pin "65") (pinfunction "PWR3_65") (pintype "bidirectional"))
    )
    (net (code "140") (name "unconnected-(U$1-PWR4-Pad66)") (class "Default")
      (node (ref "U$1") (pin "66") (pinfunction "PWR4_66") (pintype "bidirectional"))
    )
    (net (code "141") (name "unconnected-(U$1-PWR5-Pad67)") (class "Default")
      (node (ref "U$1") (pin "67") (pinfunction "PWR5_67") (pintype "bidirectional"))
    )
    (net (code "142") (name "unconnected-(U$1-PWR6-Pad68)") (class "Default")
      (node (ref "U$1") (pin "68") (pinfunction "PWR6_68") (pintype "bidirectional"))
    )
    (net (code "143") (name "unconnected-(U$1-PWR7-Pad69)") (class "Default")
      (node (ref "U$1") (pin "69") (pinfunction "PWR7_69") (pintype "bidirectional"))
    )
    (net (code "144") (name "unconnected-(U$1-RESET-N-Pad2)") (class "Default")
      (node (ref "U$1") (pin "2") (pinfunction "RESET-N_2") (pintype "bidirectional"))
    )
    (net (code "145") (name "unconnected-(U$1-SDCE-N0-Pad78)") (class "Default")
      (node (ref "U$1") (pin "78") (pinfunction "SDCE-N0_78") (pintype "bidirectional"))
    )
    (net (code "146") (name "unconnected-(U$1-SDCE-N1-Pad79)") (class "Default")
      (node (ref "U$1") (pin "79") (pinfunction "SDCE-N1_79") (pintype "bidirectional"))
    )
    (net (code "147") (name "unconnected-(U$1-SDCE-N2-Pad80)") (class "Default")
      (node (ref "U$1") (pin "80") (pinfunction "SDCE-N2_80") (pintype "bidirectional"))
    )
    (net (code "148") (name "unconnected-(U$1-SDCE-N3-Pad81)") (class "Default")
      (node (ref "U$1") (pin "81") (pinfunction "SDCE-N3_81") (pintype "bidirectional"))
    )
    (net (code "149") (name "unconnected-(U$1-SDDO8-Pad90)") (class "Default")
      (node (ref "U$1") (pin "90") (pinfunction "SDDO8_90") (pintype "bidirectional"))
    )
    (net (code "150") (name "unconnected-(U$1-SDDO9-Pad91)") (class "Default")
      (node (ref "U$1") (pin "91") (pinfunction "SDDO9_91") (pintype "bidirectional"))
    )
    (net (code "151") (name "unconnected-(U$1-SDDO10-Pad92)") (class "Default")
      (node (ref "U$1") (pin "92") (pinfunction "SDDO10_92") (pintype "bidirectional"))
    )
    (net (code "152") (name "unconnected-(U$1-SDDO11-Pad93)") (class "Default")
      (node (ref "U$1") (pin "93") (pinfunction "SDDO11_93") (pintype "bidirectional"))
    )
    (net (code "153") (name "unconnected-(U$1-SDDO12-Pad101)") (class "Default")
      (node (ref "U$1") (pin "101") (pinfunction "SDDO12_101") (pintype "bidirectional"))
    )
    (net (code "154") (name "unconnected-(U$1-SDDO13-Pad102)") (class "Default")
      (node (ref "U$1") (pin "102") (pinfunction "SDDO13_102") (pintype "bidirectional"))
    )
    (net (code "155") (name "unconnected-(U$1-SDDO14-Pad103)") (class "Default")
      (node (ref "U$1") (pin "103") (pinfunction "SDDO14_103") (pintype "bidirectional"))
    )
    (net (code "156") (name "unconnected-(U$1-SDDO15-Pad106)") (class "Default")
      (node (ref "U$1") (pin "106") (pinfunction "SDDO15_106") (pintype "bidirectional"))
    )
    (net (code "157") (name "unconnected-(U$1-SPI2-CS-Pad119)") (class "Default")
      (node (ref "U$1") (pin "119") (pinfunction "SPI2-CS_119") (pintype "bidirectional"))
    )
    (net (code "158") (name "unconnected-(U$1-SPI2-SCK-Pad122)") (class "Default")
      (node (ref "U$1") (pin "122") (pinfunction "SPI2-SCK_122") (pintype "bidirectional"))
    )
    (net (code "159") (name "unconnected-(U$1-SPI2-SI-Pad123)") (class "Default")
      (node (ref "U$1") (pin "123") (pinfunction "SPI2-SI_123") (pintype "bidirectional"))
    )
    (net (code "160") (name "unconnected-(U$1-SPI2-SO-Pad124)") (class "Default")
      (node (ref "U$1") (pin "124") (pinfunction "SPI2-SO_124") (pintype "bidirectional"))
    )
    (net (code "161") (name "unconnected-(U$1-TEST-CFG0-Pad4)") (class "Default")
      (node (ref "U$1") (pin "4") (pinfunction "TEST-CFG0_4") (pintype "bidirectional"))
    )
    (net (code "162") (name "unconnected-(U$1-TEST-CFG1-Pad5)") (class "Default")
      (node (ref "U$1") (pin "5") (pinfunction "TEST-CFG1_5") (pintype "bidirectional"))
    )
    (net (code "163") (name "unconnected-(U$1-TEST-CFG2-Pad6)") (class "Default")
      (node (ref "U$1") (pin "6") (pinfunction "TEST-CFG2_6") (pintype "bidirectional"))
    )
    (net (code "164") (name "unconnected-(U$1-TEST-EN-Pad3)") (class "Default")
      (node (ref "U$1") (pin "3") (pinfunction "TEST-EN_3") (pintype "bidirectional"))
    )
    (net (code "165") (name "unconnected-(U$1-UART-RX-Pad8)") (class "Default")
      (node (ref "U$1") (pin "8") (pinfunction "UART-RX_8") (pintype "bidirectional"))
    )
    (net (code "166") (name "unconnected-(U$1-UART-TX-Pad7)") (class "Default")
      (node (ref "U$1") (pin "7") (pinfunction "UART-TX_7") (pintype "bidirectional"))
    )
    (net (code "167") (name "unconnected-(U$1-VCC-SDR-Pad105)") (class "Default")
      (node (ref "U$1") (pin "105") (pinfunction "VCC-SDR_105") (pintype "bidirectional"))
    )
    (net (code "168") (name "unconnected-(U$1-VCC-SDR2-Pad98)") (class "Default")
      (node (ref "U$1") (pin "98") (pinfunction "VCC-SDR2_98") (pintype "bidirectional"))
    )
    (net (code "169") (name "unconnected-(U$1-VCC33A-HRST-Pad48)") (class "Default")
      (node (ref "U$1") (pin "48") (pinfunction "VCC33A-HRST_48") (pintype "bidirectional"))
    )
    (net (code "170") (name "unconnected-(U1-GPIO2{slash}SDA1-Pad3)") (class "Default")
      (node (ref "U1") (pin "3") (pinfunction "GPIO2/SDA1_3") (pintype "bidirectional"))
    )
    (net (code "171") (name "unconnected-(U1-GPIO3{slash}SCL-Pad5)") (class "Default")
      (node (ref "U1") (pin "5") (pinfunction "GPIO3/SCL_5") (pintype "bidirectional"))
    )
    (net (code "172") (name "unconnected-(U1-GPIO4{slash}GPIO_GCLK-Pad7)") (class "Default")
      (node (ref "U1") (pin "7") (pinfunction "GPIO4/GPIO_GCLK_7") (pintype "bidirectional"))
    )
    (net (code "173") (name "unconnected-(U1-GPIO5-Pad29)") (class "Default")
      (node (ref "U1") (pin "29") (pinfunction "GPIO5_29") (pintype "bidirectional"))
    )
    (net (code "174") (name "unconnected-(U1-GPIO6-Pad31)") (class "Default")
      (node (ref "U1") (pin "31") (pinfunction "GPIO6_31") (pintype "bidirectional"))
    )
    (net (code "175") (name "unconnected-(U1-GPIO7{slash}SPI_~{CE1}-Pad26)") (class "Default")
      (node (ref "U1") (pin "26") (pinfunction "GPIO7/SPI_~{CE1}_26") (pintype "bidirectional"))
    )
    (net (code "176") (name "unconnected-(U1-GPIO8{slash}SPI_~{CE0}-Pad24)") (class "Default")
      (node (ref "U1") (pin "24") (pinfunction "GPIO8/SPI_~{CE0}_24") (pintype "bidirectional"))
    )
    (net (code "177") (name "unconnected-(U1-GPIO9{slash}SPI_MISO-Pad21)") (class "Default")
      (node (ref "U1") (pin "21") (pinfunction "GPIO9/SPI_MISO_21") (pintype "bidirectional"))
    )
    (net (code "178") (name "unconnected-(U1-GPIO10{slash}SPI_MOSI-Pad19)") (class "Default")
      (node (ref "U1") (pin "19") (pinfunction "GPIO10/SPI_MOSI_19") (pintype "bidirectional"))
    )
    (net (code "179") (name "unconnected-(U1-GPIO11{slash}SPI_SCLK-Pad23)") (class "Default")
      (node (ref "U1") (pin "23") (pinfunction "GPIO11/SPI_SCLK_23") (pintype "bidirectional"))
    )
    (net (code "180") (name "unconnected-(U1-GPIO12-Pad32)") (class "Default")
      (node (ref "U1") (pin "32") (pinfunction "GPIO12_32") (pintype "bidirectional"))
    )
    (net (code "181") (name "unconnected-(U1-GPIO13-Pad33)") (class "Default")
      (node (ref "U1") (pin "33") (pinfunction "GPIO13_33") (pintype "bidirectional"))
    )
    (net (code "182") (name "unconnected-(U1-GPIO14{slash}TXD0-Pad8)") (class "Default")
      (node (ref "U1") (pin "8") (pinfunction "GPIO14/TXD0_8") (pintype "bidirectional"))
    )
    (net (code "183") (name "unconnected-(U1-GPIO15{slash}RXD0-Pad10)") (class "Default")
      (node (ref "U1") (pin "10") (pinfunction "GPIO15/RXD0_10") (pintype "bidirectional"))
    )
    (net (code "184") (name "unconnected-(U1-GPIO16-Pad36)") (class "Default")
      (node (ref "U1") (pin "36") (pinfunction "GPIO16_36") (pintype "bidirectional"))
    )
    (net (code "185") (name "unconnected-(U1-GPIO17{slash}GPIO_GEN0-Pad11)") (class "Default")
      (node (ref "U1") (pin "11") (pinfunction "GPIO17/GPIO_GEN0_11") (pintype "bidirectional"))
    )
    (net (code "186") (name "unconnected-(U1-GPIO18{slash}GPIO_GEN1-Pad12)") (class "Default")
      (node (ref "U1") (pin "12") (pinfunction "GPIO18/GPIO_GEN1_12") (pintype "bidirectional"))
    )
    (net (code "187") (name "unconnected-(U1-GPIO19-Pad35)") (class "Default")
      (node (ref "U1") (pin "35") (pinfunction "GPIO19_35") (pintype "bidirectional"))
    )
    (net (code "188") (name "unconnected-(U1-GPIO20-Pad38)") (class "Default")
      (node (ref "U1") (pin "38") (pinfunction "GPIO20_38") (pintype "bidirectional"))
    )
    (net (code "189") (name "unconnected-(U1-GPIO21-Pad40)") (class "Default")
      (node (ref "U1") (pin "40") (pinfunction "GPIO21_40") (pintype "bidirectional"))
    )
    (net (code "190") (name "unconnected-(U1-GPIO22{slash}GPIO_GEN3-Pad15)") (class "Default")
      (node (ref "U1") (pin "15") (pinfunction "GPIO22/GPIO_GEN3_15") (pintype "bidirectional"))
    )
    (net (code "191") (name "unconnected-(U1-GPIO23{slash}GPIO_GEN4-Pad16)") (class "Default")
      (node (ref "U1") (pin "16") (pinfunction "GPIO23/GPIO_GEN4_16") (pintype "bidirectional"))
    )
    (net (code "192") (name "unconnected-(U1-GPIO24{slash}GPIO_GEN5-Pad18)") (class "Default")
      (node (ref "U1") (pin "18") (pinfunction "GPIO24/GPIO_GEN5_18") (pintype "bidirectional"))
    )
    (net (code "193") (name "unconnected-(U1-GPIO25{slash}GPIO_GEN6-Pad22)") (class "Default")
      (node (ref "U1") (pin "22") (pinfunction "GPIO25/GPIO_GEN6_22") (pintype "bidirectional"))
    )
    (net (code "194") (name "unconnected-(U1-GPIO26-Pad37)") (class "Default")
      (node (ref "U1") (pin "37") (pinfunction "GPIO26_37") (pintype "bidirectional"))
    )
    (net (code "195") (name "unconnected-(U1-GPIO27{slash}GPIO_GEN2-Pad13)") (class "Default")
      (node (ref "U1") (pin "13") (pinfunction "GPIO27/GPIO_GEN2_13") (pintype "bidirectional"))
    )
    (net (code "196") (name "unconnected-(U1-ID_SC-Pad28)") (class "Default")
      (node (ref "U1") (pin "28") (pinfunction "ID_SC_28") (pintype "bidirectional"))
    )
    (net (code "197") (name "unconnected-(U1-ID_SD-Pad27)") (class "Default")
      (node (ref "U1") (pin "27") (pinfunction "ID_SD_27") (pintype "bidirectional"))
    )
    (net (code "198") (name "unconnected-(U2-TS-Pad47)") (class "Default")
      (node (ref "U2") (pin "47") (pinfunction "TS_47") (pintype "input"))
    )
  )
)
